# SR_Board.net
KiCad netlist of a schematic drawn in EAGLE
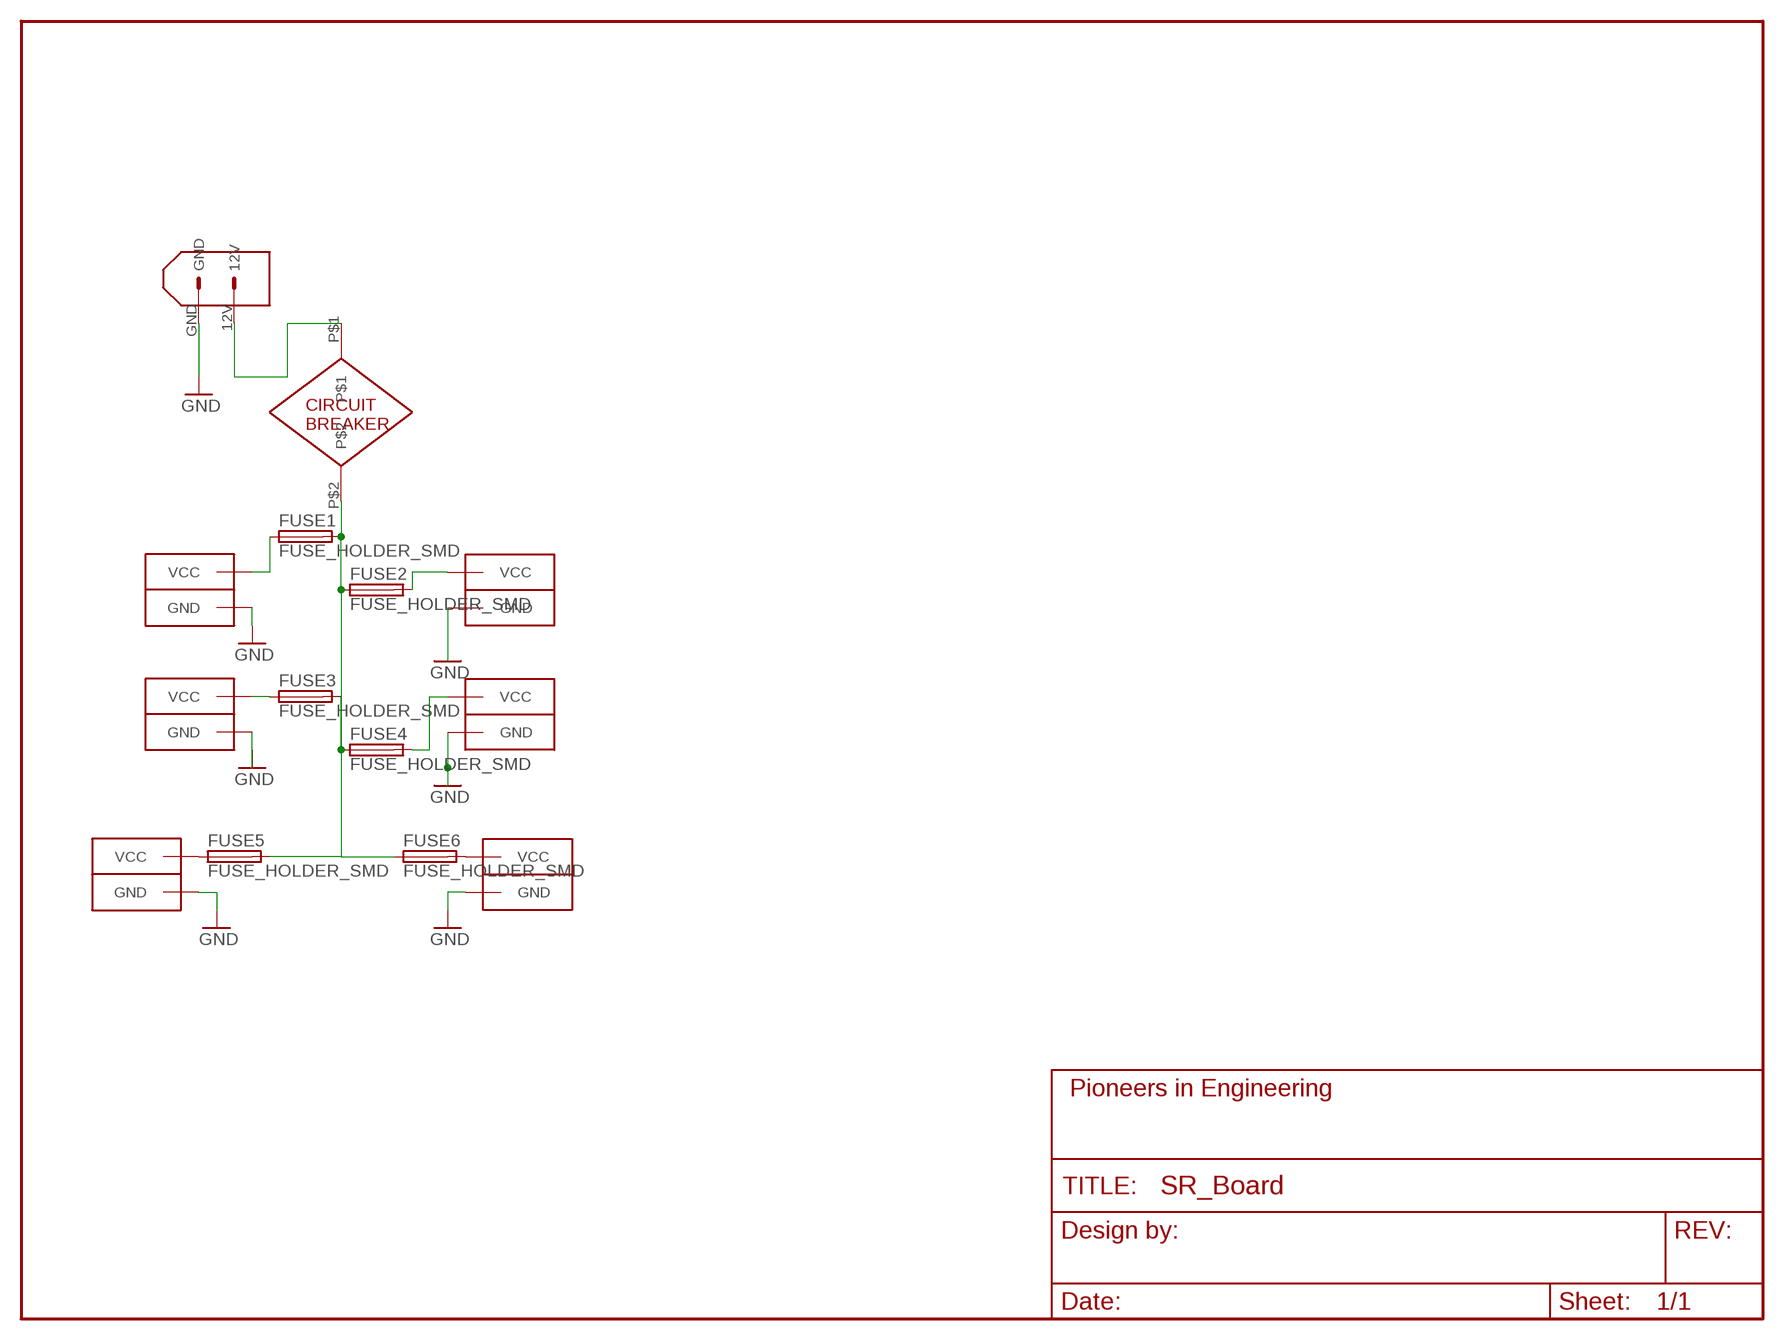
[diagram p0: schematic, sheet 1]

(export (version "E")
  (design (tool "Eeschema 10.0.6"))
  (components
    (comp (ref "CIRCUIT_BREAKER")
      (value "CIRC_BREAKER")
      (footprint "eagle-import:CIRC_BREAKER")
      (libsource (lib "eagle-import") (part "CIRC_BREAKER"))
    )
    (comp (ref "CONN1")
      (value "ANDERSONHORIZONTAL")
      (footprint "eagle-import:ANDERSON_HORIZONTAL")
      (libsource (lib "eagle-import") (part "ANDERSONHORIZONTAL"))
    )
    (comp (ref "CONN2")
      (value "ANDERSONHORIZONTAL")
      (footprint "eagle-import:ANDERSON_HORIZONTAL")
      (libsource (lib "eagle-import") (part "ANDERSONHORIZONTAL"))
    )
    (comp (ref "CONN3")
      (value "ANDERSONHORIZONTAL")
      (footprint "eagle-import:ANDERSON_HORIZONTAL")
      (libsource (lib "eagle-import") (part "ANDERSONHORIZONTAL"))
    )
    (comp (ref "CONN4")
      (value "ANDERSONHORIZONTAL")
      (footprint "eagle-import:ANDERSON_HORIZONTAL")
      (libsource (lib "eagle-import") (part "ANDERSONHORIZONTAL"))
    )
    (comp (ref "CONN5")
      (value "ANDERSONHORIZONTAL")
      (footprint "eagle-import:ANDERSON_HORIZONTAL")
      (libsource (lib "eagle-import") (part "ANDERSONHORIZONTAL"))
    )
    (comp (ref "CONN6")
      (value "ANDERSONHORIZONTAL")
      (footprint "eagle-import:ANDERSON_HORIZONTAL")
      (libsource (lib "eagle-import") (part "ANDERSONHORIZONTAL"))
    )
    (comp (ref "FUSE1")
      (value "FUSE_HOLDER_SMD")
      (footprint "eagle-import:FUSE_HOLDER_SMD")
      (libsource (lib "eagle-import") (part "FUSE_HOLDER_SMD"))
    )
    (comp (ref "FUSE2")
      (value "FUSE_HOLDER_SMD")
      (footprint "eagle-import:FUSE_HOLDER_SMD")
      (libsource (lib "eagle-import") (part "FUSE_HOLDER_SMD"))
    )
    (comp (ref "FUSE3")
      (value "FUSE_HOLDER_SMD")
      (footprint "eagle-import:FUSE_HOLDER_SMD")
      (libsource (lib "eagle-import") (part "FUSE_HOLDER_SMD"))
    )
    (comp (ref "FUSE4")
      (value "FUSE_HOLDER_SMD")
      (footprint "eagle-import:FUSE_HOLDER_SMD")
      (libsource (lib "eagle-import") (part "FUSE_HOLDER_SMD"))
    )
    (comp (ref "FUSE5")
      (value "FUSE_HOLDER_SMD")
      (footprint "eagle-import:FUSE_HOLDER_SMD")
      (libsource (lib "eagle-import") (part "FUSE_HOLDER_SMD"))
    )
    (comp (ref "FUSE6")
      (value "FUSE_HOLDER_SMD")
      (footprint "eagle-import:FUSE_HOLDER_SMD")
      (libsource (lib "eagle-import") (part "FUSE_HOLDER_SMD"))
    )
    (comp (ref "U$1")
      (value "XT60CONNECTOR")
      (footprint "eagle-import:XT60CONNECTOR")
      (fields (field (name "PARTNUMBER") "PRT-10474 "))
      (libsource (lib "eagle-import") (part "XT60CONNECTOR"))
    )
  )
  (nets
    (net (code "1") (name "GND") (class "Default")
      (node (ref "CONN2") (pin "PIN1") (pinfunction "GND_PIN1") (pintype "bidirectional"))
      (node (ref "CONN2") (pin "PIN1-LEAD") (pinfunction "GND_PIN1-LEAD") (pintype "bidirectional"))
      (node (ref "CONN3") (pin "PIN1") (pinfunction "GND_PIN1") (pintype "bidirectional"))
      (node (ref "CONN3") (pin "PIN1-LEAD") (pinfunction "GND_PIN1-LEAD") (pintype "bidirectional"))
      (node (ref "CONN5") (pin "PIN1") (pinfunction "GND_PIN1") (pintype "bidirectional"))
      (node (ref "CONN5") (pin "PIN1-LEAD") (pinfunction "GND_PIN1-LEAD") (pintype "bidirectional"))
      (node (ref "CONN6") (pin "PIN1") (pinfunction "GND_PIN1") (pintype "bidirectional"))
      (node (ref "CONN6") (pin "PIN1-LEAD") (pinfunction "GND_PIN1-LEAD") (pintype "bidirectional"))
      (node (ref "U$1") (pin "GND") (pinfunction "GND_GND") (pintype "bidirectional"))
    )
    (net (code "2") (name "Net-(CIRCUIT_BREAKER-PadP$1)") (class "Default")
      (node (ref "CIRCUIT_BREAKER") (pin "P$1") (pinfunction "P$1_P$1") (pintype "bidirectional"))
      (node (ref "U$1") (pin "12V") (pinfunction "12V_12V") (pintype "bidirectional"))
    )
    (net (code "3") (name "Net-(CIRCUIT_BREAKER-PadP$2)") (class "Default")
      (node (ref "CIRCUIT_BREAKER") (pin "P$2") (pinfunction "P$2_P$2") (pintype "bidirectional"))
      (node (ref "FUSE1") (pin "P$2_DOWN") (pinfunction "2_P$2_DOWN") (pintype "passive"))
      (node (ref "FUSE1") (pin "P$2_UP") (pinfunction "2_P$2_UP") (pintype "passive"))
      (node (ref "FUSE2") (pin "P$1_DOWN") (pinfunction "1_P$1_DOWN") (pintype "passive"))
      (node (ref "FUSE2") (pin "P$1_UP") (pinfunction "1_P$1_UP") (pintype "passive"))
      (node (ref "FUSE3") (pin "P$2_DOWN") (pinfunction "2_P$2_DOWN") (pintype "passive"))
      (node (ref "FUSE3") (pin "P$2_UP") (pinfunction "2_P$2_UP") (pintype "passive"))
      (node (ref "FUSE4") (pin "P$1_DOWN") (pinfunction "1_P$1_DOWN") (pintype "passive"))
      (node (ref "FUSE4") (pin "P$1_UP") (pinfunction "1_P$1_UP") (pintype "passive"))
      (node (ref "FUSE5") (pin "P$2_DOWN") (pinfunction "2_P$2_DOWN") (pintype "passive"))
      (node (ref "FUSE5") (pin "P$2_UP") (pinfunction "2_P$2_UP") (pintype "passive"))
      (node (ref "FUSE6") (pin "P$1_DOWN") (pinfunction "1_P$1_DOWN") (pintype "passive"))
      (node (ref "FUSE6") (pin "P$1_UP") (pinfunction "1_P$1_UP") (pintype "passive"))
    )
    (net (code "4") (name "Net-(CONN1-GND-PadPIN1)") (class "Default")
      (node (ref "CONN1") (pin "PIN1") (pinfunction "GND_PIN1") (pintype "bidirectional"))
      (node (ref "CONN1") (pin "PIN1-LEAD") (pinfunction "GND_PIN1-LEAD") (pintype "bidirectional"))
    )
    (net (code "5") (name "Net-(CONN1-VCC-PadPIN2)") (class "Default")
      (node (ref "CONN1") (pin "PIN2") (pinfunction "VCC_PIN2") (pintype "bidirectional"))
      (node (ref "CONN1") (pin "PIN2-LEAD") (pinfunction "VCC_PIN2-LEAD") (pintype "bidirectional"))
      (node (ref "FUSE3") (pin "P$1_DOWN") (pinfunction "1_P$1_DOWN") (pintype "passive"))
      (node (ref "FUSE3") (pin "P$1_UP") (pinfunction "1_P$1_UP") (pintype "passive"))
    )
    (net (code "6") (name "Net-(CONN2-VCC-PadPIN2)") (class "Default")
      (node (ref "CONN2") (pin "PIN2") (pinfunction "VCC_PIN2") (pintype "bidirectional"))
      (node (ref "CONN2") (pin "PIN2-LEAD") (pinfunction "VCC_PIN2-LEAD") (pintype "bidirectional"))
      (node (ref "FUSE1") (pin "P$1_DOWN") (pinfunction "1_P$1_DOWN") (pintype "passive"))
      (node (ref "FUSE1") (pin "P$1_UP") (pinfunction "1_P$1_UP") (pintype "passive"))
    )
    (net (code "7") (name "Net-(CONN3-VCC-PadPIN2)") (class "Default")
      (node (ref "CONN3") (pin "PIN2") (pinfunction "VCC_PIN2") (pintype "bidirectional"))
      (node (ref "CONN3") (pin "PIN2-LEAD") (pinfunction "VCC_PIN2-LEAD") (pintype "bidirectional"))
      (node (ref "FUSE5") (pin "P$1_DOWN") (pinfunction "1_P$1_DOWN") (pintype "passive"))
      (node (ref "FUSE5") (pin "P$1_UP") (pinfunction "1_P$1_UP") (pintype "passive"))
    )
    (net (code "8") (name "Net-(CONN4-GND-PadPIN1)") (class "Default")
      (node (ref "CONN4") (pin "PIN1") (pinfunction "GND_PIN1") (pintype "bidirectional"))
      (node (ref "CONN4") (pin "PIN1-LEAD") (pinfunction "GND_PIN1-LEAD") (pintype "bidirectional"))
    )
    (net (code "9") (name "Net-(CONN4-VCC-PadPIN2)") (class "Default")
      (node (ref "CONN4") (pin "PIN2") (pinfunction "VCC_PIN2") (pintype "bidirectional"))
      (node (ref "CONN4") (pin "PIN2-LEAD") (pinfunction "VCC_PIN2-LEAD") (pintype "bidirectional"))
      (node (ref "FUSE2") (pin "P$2_DOWN") (pinfunction "2_P$2_DOWN") (pintype "passive"))
      (node (ref "FUSE2") (pin "P$2_UP") (pinfunction "2_P$2_UP") (pintype "passive"))
    )
    (net (code "10") (name "Net-(CONN5-VCC-PadPIN2)") (class "Default")
      (node (ref "CONN5") (pin "PIN2") (pinfunction "VCC_PIN2") (pintype "bidirectional"))
      (node (ref "CONN5") (pin "PIN2-LEAD") (pinfunction "VCC_PIN2-LEAD") (pintype "bidirectional"))
      (node (ref "FUSE4") (pin "P$2_DOWN") (pinfunction "2_P$2_DOWN") (pintype "passive"))
      (node (ref "FUSE4") (pin "P$2_UP") (pinfunction "2_P$2_UP") (pintype "passive"))
    )
    (net (code "11") (name "Net-(CONN6-VCC-PadPIN2)") (class "Default")
      (node (ref "CONN6") (pin "PIN2") (pinfunction "VCC_PIN2") (pintype "bidirectional"))
      (node (ref "CONN6") (pin "PIN2-LEAD") (pinfunction "VCC_PIN2-LEAD") (pintype "bidirectional"))
      (node (ref "FUSE6") (pin "P$2_DOWN") (pinfunction "2_P$2_DOWN") (pintype "passive"))
      (node (ref "FUSE6") (pin "P$2_UP") (pinfunction "2_P$2_UP") (pintype "passive"))
    )
  )
)
